# LoRa.net
KiCad netlist of a schematic drawn in Altium Designer
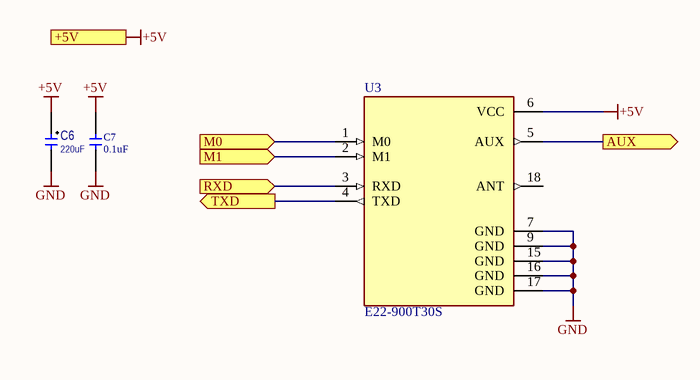
[diagram p0: LoRa.SchDoc]

(export (version "E")
  (design (tool "Eeschema 10.0.6"))
  (components
    (comp (ref "C6")
      (value "220uF")
      (footprint "TECAP C")
      (description "Capacitor Polar")
      (fields (field (name "Comment") "TECAP C 220uF * X7R"))
      (libsource (lib "!main") (part "CapacitorP"))
    )
    (comp (ref "C7")
      (value "0.1uF")
      (footprint "CERCAP 0402")
      (description "Capacitor")
      (fields (field (name "Comment") "CERCAP 0402 0.1uF * X7R"))
      (libsource (lib "!main") (part "!Capacitor"))
    )
    (comp (ref "U3")
      (value "E22-900T30S")
      (footprint "E22-900T30S")
      (description "LORA RF")
      (libsource (lib "Wireless") (part "E22-900T30S"))
    )
  )
  (nets
    (net (code "1") (name "+5V") (class "Default")
      (node (ref "C6") (pin "1") (pinfunction "+_1") (pintype "passive"))
      (node (ref "C7") (pin "2") (pintype "passive"))
      (node (ref "U3") (pin "6") (pinfunction "VCC_6") (pintype "power_in"))
    )
    (net (code "2") (name "/AUX") (class "Default")
      (node (ref "U3") (pin "5") (pinfunction "AUX_5") (pintype "output"))
    )
    (net (code "3") (name "/M0") (class "Default")
      (node (ref "U3") (pin "1") (pinfunction "M0_1") (pintype "input"))
    )
    (net (code "4") (name "/M1") (class "Default")
      (node (ref "U3") (pin "2") (pinfunction "M1_2") (pintype "input"))
    )
    (net (code "5") (name "/RXD") (class "Default")
      (node (ref "U3") (pin "3") (pinfunction "RXD_3") (pintype "input"))
    )
    (net (code "6") (name "/TXD") (class "Default")
      (node (ref "U3") (pin "4") (pinfunction "TXD_4") (pintype "output"))
    )
    (net (code "7") (name "GND") (class "Default")
      (node (ref "C6") (pin "2") (pinfunction "-_2") (pintype "passive"))
      (node (ref "C7") (pin "1") (pintype "passive"))
      (node (ref "U3") (pin "15") (pinfunction "GND_15") (pintype "power_in"))
      (node (ref "U3") (pin "16") (pinfunction "GND_16") (pintype "power_in"))
      (node (ref "U3") (pin "17") (pinfunction "GND_17") (pintype "power_in"))
      (node (ref "U3") (pin "7") (pinfunction "GND_7") (pintype "power_in"))
      (node (ref "U3") (pin "9") (pinfunction "GND_9") (pintype "power_in"))
    )
    (net (code "8") (name "unconnected-(U3-ANT-Pad18)") (class "Default")
      (node (ref "U3") (pin "18") (pinfunction "ANT_18") (pintype "output"))
    )
  )
)
